# S-GRAFENO.net
KiCad netlist of a schematic drawn in Altium Designer
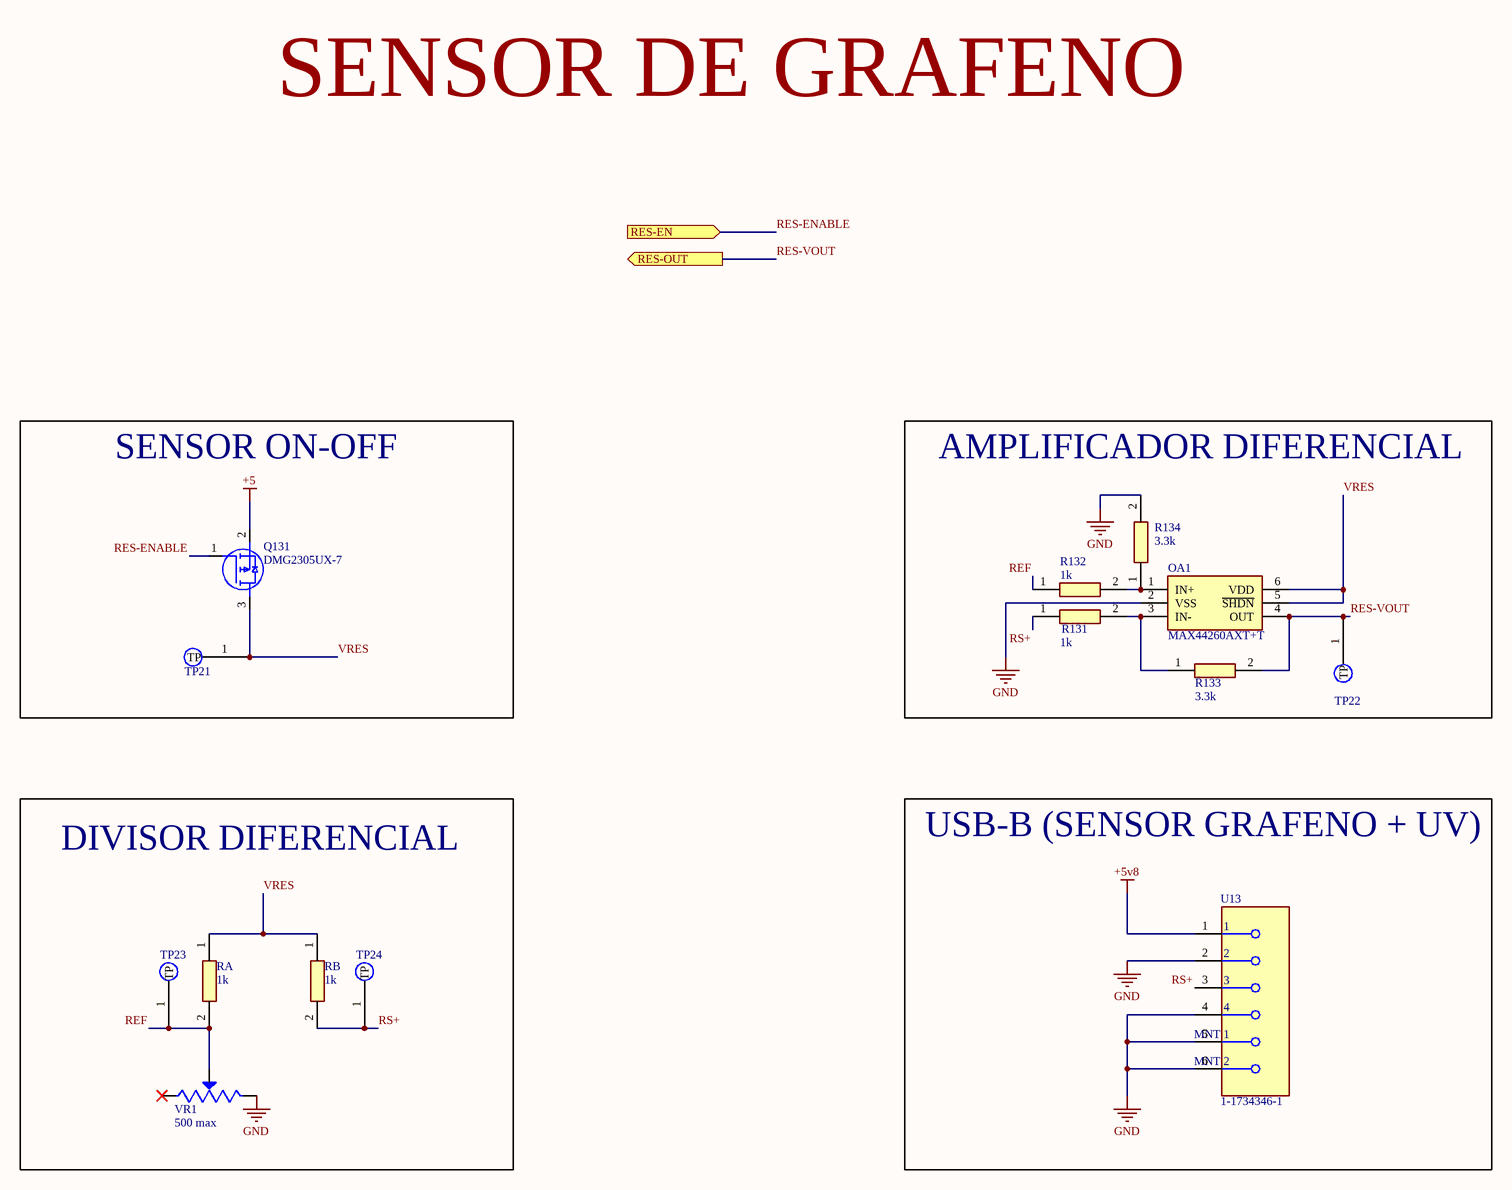
[diagram p0: S-GRAFENO.SchDoc]

(export (version "E")
  (design (tool "Eeschema 10.0.6"))
  (components
    (comp (ref "OA1")
      (value "MAX44260AXT+T")
      (footprint "SamacSys:SOT65P218X110-6N")
      (description "Integrated Circuit")
      (fields (field (name "MOUSER PART NUMBER") "700-MAX44260AXT+T"))
      (libsource (lib "*") (part "MAX44260AXT+T"))
    )
    (comp (ref "Q131")
      (value "DMG2305UX-7")
      (footprint "SamacSys:SOT96P240X115-3N")
      (description "MOSFET (P-Channel)")
      (fields (field (name "MOUSER PART NUMBER") "621-DMG2305UX-7"))
      (libsource (lib "*") (part "DMG2305UX-7"))
    )
    (comp (ref "R131")
      (value "1k")
      (footprint "SamacSys:ERA6AEB101V")
      (description "Resistor")
      (fields
        (field (name "MANUFACTURER_PART_NUMBER") "ERA-6ARW102V")
        (field (name "MOUSER PART NUMBER") "667-ERA-6ARW102V")
      )
      (libsource (lib "*") (part "ERA-6ARW102V"))
    )
    (comp (ref "R132")
      (value "1k")
      (footprint "SamacSys:ERA6AEB101V")
      (description "Resistor")
      (fields
        (field (name "MANUFACTURER_PART_NUMBER") "ERA-6ARW102V")
        (field (name "MOUSER PART NUMBER") "667-ERA-6ARW102V")
      )
      (libsource (lib "*") (part "ERA-6ARW102V"))
    )
    (comp (ref "R133")
      (value "3.3k")
      (footprint "SamacSys:ERJP06D1000V")
      (description "Resistor")
      (fields (field (name "MANUFACTURER_PART_NUMBER") "ERJ-P06D3301V"))
      (libsource (lib "*") (part "ERJ-P06D3301V"))
    )
    (comp (ref "R134")
      (value "3.3k")
      (footprint "SamacSys:ERJP06D1000V")
      (description "Resistor")
      (fields (field (name "MANUFACTURER_PART_NUMBER") "ERJ-P06D3301V"))
      (libsource (lib "") (part "ERJ-P06D3301V_1"))
    )
    (comp (ref "RA")
      (value "1k")
      (footprint "SamacSys:ERA6AEB101V")
      (description "Resistor")
      (fields
        (field (name "MANUFACTURER_PART_NUMBER") "ERA-6ARW102V")
        (field (name "MOUSER PART NUMBER") "667-ERA-6ARW102V")
      )
      (libsource (lib "") (part "ERA-6ARW102V_1"))
    )
    (comp (ref "RB")
      (value "1k")
      (footprint "SamacSys:ERA6AEB101V")
      (description "Resistor")
      (fields
        (field (name "MANUFACTURER_PART_NUMBER") "ERA-6ARW102V")
        (field (name "MOUSER PART NUMBER") "667-ERA-6ARW102V")
      )
      (libsource (lib "") (part "ERA-6ARW102V_1"))
    )
    (comp (ref "TP21")
      (value "Testpoint")
      (footprint "Testpoint_TH")
      (libsource (lib "headers") (part "Testpoint"))
    )
    (comp (ref "TP22")
      (value "Testpoint")
      (footprint "Testpoint_TH")
      (libsource (lib "headers") (part "Testpoint"))
    )
    (comp (ref "TP23")
      (value "Testpoint")
      (footprint "Testpoint_TH")
      (libsource (lib "headers") (part "Testpoint"))
    )
    (comp (ref "TP24")
      (value "Testpoint")
      (footprint "Testpoint_TH")
      (libsource (lib "headers") (part "Testpoint"))
    )
    (comp (ref "U13")
      (value "1-1734346-1")
      (footprint "FP-1-1734346-1-MFG")
      (description "CONN RCPT USB2.0 TYPEB 4P SMD RA")
      (fields
        (field (name "MANUFACTURER") "TE")
        (field (name "OCTOPART") "https://octopart.com/1-1734346-1-te+connectivity-43171491")
      )
      (libsource (lib "Altium Content Vault") (part "3cf8230c7ca2247c71501eddf00a6f6"))
    )
    (comp (ref "VR1")
      (value "500 max")
      (footprint "TRIM_3296W-1-501LF")
      (description "Recortador, Cermet, Descanso 500 Ohms, PCB, 25 Vueltas, Pwr-Rtg 0.5W ¦ Bourns 3296W-1-501LF")
      (fields (field (name "MF") "Bourns") (field (name "MP") "3296W-1-501LF"))
      (libsource (lib "3296W-1-501LF") (part "3296W-1-501LF"))
    )
  )
  (nets
    (net (code "1") (name "+5") (class "Default")
      (node (ref "Q131") (pin "2") (pinfunction "S_2") (pintype "passive"))
    )
    (net (code "2") (name "+5v8") (class "Default")
      (node (ref "U13") (pin "1") (pinfunction "1_1") (pintype "passive"))
    )
    (net (code "3") (name "/REF") (class "Default")
      (node (ref "R132") (pin "1") (pinfunction "1_1") (pintype "passive"))
      (node (ref "RA") (pin "2") (pinfunction "2_2") (pintype "passive"))
      (node (ref "TP23") (pin "1") (pinfunction "TP_1") (pintype "passive"))
      (node (ref "VR1") (pin "2") (pinfunction "WIPER_2") (pintype "passive"))
    )
    (net (code "4") (name "/RES-ENABLE") (class "Default")
      (node (ref "Q131") (pin "1") (pinfunction "G_1") (pintype "passive"))
    )
    (net (code "5") (name "/RES-VOUT") (class "Default")
      (node (ref "OA1") (pin "4") (pinfunction "OUT_4") (pintype "passive"))
      (node (ref "R133") (pin "2") (pinfunction "2_2") (pintype "passive"))
      (node (ref "TP22") (pin "1") (pinfunction "TP_1") (pintype "passive"))
    )
    (net (code "6") (name "/RS+") (class "Default")
      (node (ref "R131") (pin "1") (pinfunction "1_1") (pintype "passive"))
      (node (ref "RB") (pin "2") (pinfunction "2_2") (pintype "passive"))
      (node (ref "TP24") (pin "1") (pinfunction "TP_1") (pintype "passive"))
      (node (ref "U13") (pin "3") (pinfunction "3_3") (pintype "passive"))
    )
    (net (code "7") (name "/VRES") (class "Default")
      (node (ref "OA1") (pin "5") (pinfunction "~{SHDN}_5") (pintype "passive"))
      (node (ref "OA1") (pin "6") (pinfunction "VDD_6") (pintype "passive"))
      (node (ref "Q131") (pin "3") (pinfunction "D_3") (pintype "passive"))
      (node (ref "RA") (pin "1") (pinfunction "1_1") (pintype "passive"))
      (node (ref "RB") (pin "1") (pinfunction "1_1") (pintype "passive"))
      (node (ref "TP21") (pin "1") (pinfunction "TP_1") (pintype "passive"))
    )
    (net (code "8") (name "GND") (class "Default")
      (node (ref "OA1") (pin "2") (pinfunction "VSS_2") (pintype "passive"))
      (node (ref "R134") (pin "2") (pinfunction "2_2") (pintype "passive"))
      (node (ref "U13") (pin "2") (pinfunction "2_2") (pintype "passive"))
      (node (ref "U13") (pin "4") (pinfunction "4_4") (pintype "passive"))
      (node (ref "U13") (pin "5") (pinfunction "MNT_1_5") (pintype "passive"))
      (node (ref "U13") (pin "6") (pinfunction "MNT_2_6") (pintype "passive"))
      (node (ref "VR1") (pin "3") (pinfunction "CW_3") (pintype "passive"))
    )
    (net (code "9") (name "Net-(OA1-IN+)") (class "Default")
      (node (ref "OA1") (pin "1") (pinfunction "IN+_1") (pintype "passive"))
      (node (ref "R132") (pin "2") (pinfunction "2_2") (pintype "passive"))
      (node (ref "R134") (pin "1") (pinfunction "1_1") (pintype "passive"))
    )
    (net (code "10") (name "Net-(OA1-IN-)") (class "Default")
      (node (ref "OA1") (pin "3") (pinfunction "IN-_3") (pintype "passive"))
      (node (ref "R131") (pin "2") (pinfunction "2_2") (pintype "passive"))
      (node (ref "R133") (pin "1") (pinfunction "1_1") (pintype "passive"))
    )
    (net (code "11") (name "unconnected-(VR1-CCW-Pad1)") (class "Default")
      (node (ref "VR1") (pin "1") (pinfunction "CCW_1") (pintype "passive+no_connect"))
    )
  )
)
